# RAM.net
KiCad netlist of a schematic drawn in Altium Designer
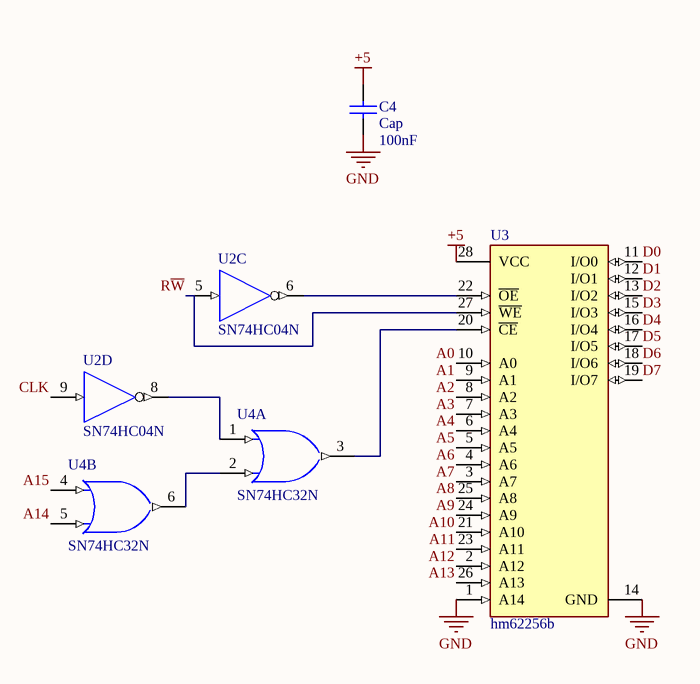
[diagram p0: RAM.SchDoc]

(export (version "E")
  (design (tool "Eeschema 10.0.6"))
  (components
    (comp (ref "C4")
      (value "Cap")
      (footprint "Ceramic Capacitor")
      (description "Capacitor")
      (fields (field (name "ALTIUM_VALUE") "100nF") (field (name "PUBLISHER") "Altium Limited"))
      (libsource (lib "Miscellaneous Devices") (part "Cap"))
    )
    (comp (ref "U2")
      (value "SN74HC04N")
      (footprint "N0014A")
      (description "Hex Inverters, N0014A, TUBE")
      (fields
        (field (name "MANUFACTURER") "Texas Instruments")
        (field (name "GENERIC PART NUMBER") "SN74HC04")
      )
      (libsource (lib "Altium Content Vault") (part "TI-CD_SNX4XXXXXX4X_19A-14"))
    )
    (comp (ref "U3")
      (value "hm62256b")
      (footprint "FP-28P6-MFG")
      (description "RAM")
      (fields
        (field (name "MANUFACTURER PART NUMBER") "AT28C256-15PU")
        (field (name "MANUFACTURER") "Microchip")
      )
      (libsource (lib "Altium Content Vault") (part "df06beef5d7b4d1cd730806cb3934f7"))
    )
    (comp (ref "U4")
      (value "SN74HC32N")
      (footprint "N0014A")
      (description "Quadruple 2-Input Positive-OR Gates, N0014A, TUBE")
      (fields
        (field (name "MANUFACTURER") "Texas Instruments")
        (field (name "GENERIC PART NUMBER") "SN74HC32")
      )
      (libsource (lib "Altium Content Vault") (part "TI-OR-4-2IN-14"))
    )
  )
  (nets
    (net (code "1") (name "+5") (class "Default")
      (node (ref "C4") (pin "1") (pinfunction "1_1") (pintype "passive"))
      (node (ref "U3") (pin "28") (pinfunction "VCC_28") (pintype "power_in"))
    )
    (net (code "2") (name "/A0") (class "Default")
      (node (ref "U3") (pin "10") (pinfunction "A0_10") (pintype "input"))
    )
    (net (code "3") (name "/A1") (class "Default")
      (node (ref "U3") (pin "9") (pinfunction "A1_9") (pintype "input"))
    )
    (net (code "4") (name "/A2") (class "Default")
      (node (ref "U3") (pin "8") (pinfunction "A2_8") (pintype "input"))
    )
    (net (code "5") (name "/A3") (class "Default")
      (node (ref "U3") (pin "7") (pinfunction "A3_7") (pintype "input"))
    )
    (net (code "6") (name "/A4") (class "Default")
      (node (ref "U3") (pin "6") (pinfunction "A4_6") (pintype "input"))
    )
    (net (code "7") (name "/A5") (class "Default")
      (node (ref "U3") (pin "5") (pinfunction "A5_5") (pintype "input"))
    )
    (net (code "8") (name "/A6") (class "Default")
      (node (ref "U3") (pin "4") (pinfunction "A6_4") (pintype "input"))
    )
    (net (code "9") (name "/A7") (class "Default")
      (node (ref "U3") (pin "3") (pinfunction "A7_3") (pintype "input"))
    )
    (net (code "10") (name "/A8") (class "Default")
      (node (ref "U3") (pin "25") (pinfunction "A8_25") (pintype "input"))
    )
    (net (code "11") (name "/A9") (class "Default")
      (node (ref "U3") (pin "24") (pinfunction "A9_24") (pintype "input"))
    )
    (net (code "12") (name "/A10") (class "Default")
      (node (ref "U3") (pin "21") (pinfunction "A10_21") (pintype "input"))
    )
    (net (code "13") (name "/A11") (class "Default")
      (node (ref "U3") (pin "23") (pinfunction "A11_23") (pintype "input"))
    )
    (net (code "14") (name "/A12") (class "Default")
      (node (ref "U3") (pin "2") (pinfunction "A12_2") (pintype "input"))
    )
    (net (code "15") (name "/A13") (class "Default")
      (node (ref "U3") (pin "26") (pinfunction "A13_26") (pintype "input"))
    )
    (net (code "16") (name "/A14") (class "Default")
      (node (ref "U4") (pin "5") (pinfunction "2B_5") (pintype "input"))
    )
    (net (code "17") (name "/A15") (class "Default")
      (node (ref "U4") (pin "4") (pinfunction "2A_4") (pintype "input"))
    )
    (net (code "18") (name "/CLK") (class "Default")
      (node (ref "U2") (pin "9") (pinfunction "4A_9") (pintype "input"))
    )
    (net (code "19") (name "/D0") (class "Default")
      (node (ref "U3") (pin "11") (pinfunction "I/O0_11") (pintype "bidirectional"))
    )
    (net (code "20") (name "/D1") (class "Default")
      (node (ref "U3") (pin "12") (pinfunction "I/O1_12") (pintype "bidirectional"))
    )
    (net (code "21") (name "/D2") (class "Default")
      (node (ref "U3") (pin "13") (pinfunction "I/O2_13") (pintype "bidirectional"))
    )
    (net (code "22") (name "/D3") (class "Default")
      (node (ref "U3") (pin "15") (pinfunction "I/O3_15") (pintype "bidirectional"))
    )
    (net (code "23") (name "/D4") (class "Default")
      (node (ref "U3") (pin "16") (pinfunction "I/O4_16") (pintype "bidirectional"))
    )
    (net (code "24") (name "/D5") (class "Default")
      (node (ref "U3") (pin "17") (pinfunction "I/O5_17") (pintype "bidirectional"))
    )
    (net (code "25") (name "/D6") (class "Default")
      (node (ref "U3") (pin "18") (pinfunction "I/O6_18") (pintype "bidirectional"))
    )
    (net (code "26") (name "/D7") (class "Default")
      (node (ref "U3") (pin "19") (pinfunction "I/O7_19") (pintype "bidirectional"))
    )
    (net (code "27") (name "/R~{W}") (class "Default")
      (node (ref "U2") (pin "5") (pinfunction "3A_5") (pintype "input"))
      (node (ref "U3") (pin "27") (pinfunction "~{WE}_27") (pintype "input"))
    )
    (net (code "28") (name "GND") (class "Default")
      (node (ref "C4") (pin "2") (pinfunction "2_2") (pintype "passive"))
      (node (ref "U3") (pin "1") (pinfunction "A14_1") (pintype "input"))
      (node (ref "U3") (pin "14") (pinfunction "GND_14") (pintype "power_in"))
    )
    (net (code "29") (name "Net-(U2C-~{3Y})") (class "Default")
      (node (ref "U2") (pin "6") (pinfunction "~{3Y}_6") (pintype "output"))
      (node (ref "U3") (pin "22") (pinfunction "~{OE}_22") (pintype "input"))
    )
    (net (code "30") (name "Net-(U2D-~{4Y})") (class "Default")
      (node (ref "U2") (pin "8") (pinfunction "~{4Y}_8") (pintype "output"))
      (node (ref "U4") (pin "1") (pinfunction "1A_1") (pintype "input"))
    )
    (net (code "31") (name "Net-(U3-~{CE})") (class "Default")
      (node (ref "U3") (pin "20") (pinfunction "~{CE}_20") (pintype "input"))
      (node (ref "U4") (pin "3") (pinfunction "1Y_3") (pintype "output"))
    )
    (net (code "32") (name "Net-(U4A-1B)") (class "Default")
      (node (ref "U4") (pin "2") (pinfunction "1B_2") (pintype "input"))
      (node (ref "U4") (pin "6") (pinfunction "2Y_6") (pintype "output"))
    )
  )
)
